# amp.net
KiCad netlist of a schematic drawn in Altium Designer
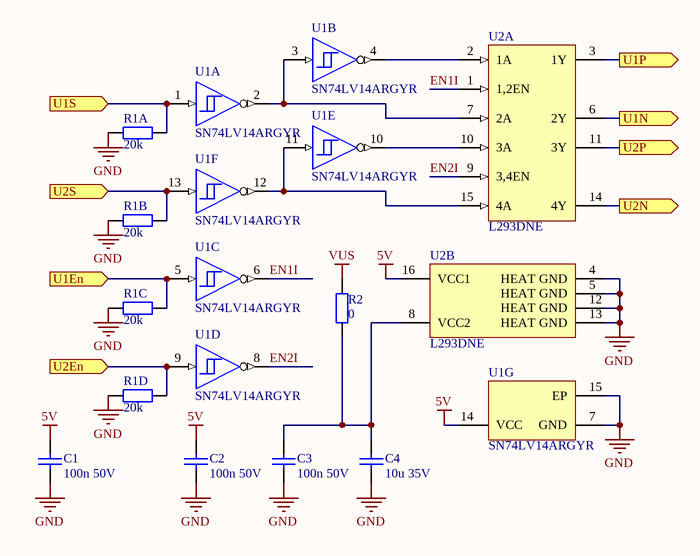
[diagram p0: amp.SchDoc]

(export (version "E")
  (design (tool "Eeschema 10.0.6"))
  (components
    (comp (ref "C1")
      (value "100n 50V")
      (footprint "C-0603-M")
      (description "Capacitor 100n 50V")
      (libsource (lib "Passives") (part "C-0603-100n-50V"))
    )
    (comp (ref "C2")
      (value "100n 50V")
      (footprint "C-0603-M")
      (description "Capacitor 100n 50V")
      (libsource (lib "Passives") (part "C-0603-100n-50V"))
    )
    (comp (ref "C3")
      (value "100n 50V")
      (footprint "C-0603-M")
      (description "Capacitor 100n 50V")
      (libsource (lib "Passives") (part "C-0603-100n-50V"))
    )
    (comp (ref "C4")
      (value "10u 35V")
      (footprint "C-0805-M")
      (description "3")
      (libsource (lib "Passives") (part "C-0805-10u-25V"))
    )
    (comp (ref "R1")
      (value "20k")
      (footprint "CAC-50P200X100-8N")
      (description "Resistor Array 4x20k")
      (libsource (lib "Passives") (part "R-4x20k"))
    )
    (comp (ref "R2")
      (value "0")
      (footprint "R-0603-M")
      (description "Resistor 0")
      (libsource (lib "Passives") (part "R-0603-0"))
    )
    (comp (ref "U1")
      (value "SN74LV14ARGYR")
      (footprint "RGY0014A_V")
      (description "Hex Schmitt-Trigger Inverters, RGY0014A, LARGE T&R")
      (fields
        (field (name "GENERIC PART NUMBER") "SN74LV14A")
        (field (name "MANUFACTURER") "Texas Instruments")
      )
      (libsource (lib "Altium Content Vault") (part "TI-SN74XXXXX4X-RGY0014A-14-SCHMITT"))
    )
    (comp (ref "U2")
      (value "L293DNE")
      (footprint "NE0016A")
      (fields (field (name "TOLERANCE") "10%"))
      (libsource (lib "Altium Content Vault") (part "TI-L293-NE16"))
    )
  )
  (nets
    (net (code "1") (name "/EN1I") (class "Default")
      (node (ref "U1") (pin "6") (pinfunction "~{3Y}_6") (pintype "output"))
      (node (ref "U2") (pin "1") (pinfunction "1,2EN_1") (pintype "input"))
    )
    (net (code "2") (name "/EN2I") (class "Default")
      (node (ref "U1") (pin "8") (pinfunction "~{4Y}_8") (pintype "output"))
      (node (ref "U2") (pin "9") (pinfunction "3,4EN_9") (pintype "input"))
    )
    (net (code "3") (name "/U1En") (class "Default")
      (node (ref "R1") (pin "6") (pinfunction "6_6") (pintype "passive"))
      (node (ref "U1") (pin "5") (pinfunction "3A_5") (pintype "input"))
    )
    (net (code "4") (name "/U1N") (class "Default")
      (node (ref "U2") (pin "6") (pinfunction "2Y_6") (pintype "tri_state"))
    )
    (net (code "5") (name "/U1P") (class "Default")
      (node (ref "U2") (pin "3") (pinfunction "1Y_3") (pintype "tri_state"))
    )
    (net (code "6") (name "/U1S") (class "Default")
      (node (ref "R1") (pin "8") (pinfunction "8_8") (pintype "passive"))
      (node (ref "U1") (pin "1") (pinfunction "1A_1") (pintype "input"))
    )
    (net (code "7") (name "/U2En") (class "Default")
      (node (ref "R1") (pin "5") (pinfunction "5_5") (pintype "passive"))
      (node (ref "U1") (pin "9") (pinfunction "4A_9") (pintype "input"))
    )
    (net (code "8") (name "/U2N") (class "Default")
      (node (ref "U2") (pin "14") (pinfunction "4Y_14") (pintype "tri_state"))
    )
    (net (code "9") (name "/U2P") (class "Default")
      (node (ref "U2") (pin "11") (pinfunction "3Y_11") (pintype "tri_state"))
    )
    (net (code "10") (name "/U2S") (class "Default")
      (node (ref "R1") (pin "7") (pinfunction "7_7") (pintype "passive"))
      (node (ref "U1") (pin "13") (pinfunction "6A_13") (pintype "input"))
    )
    (net (code "11") (name "5V") (class "Default")
      (node (ref "C1") (pin "2") (pinfunction "2_2") (pintype "passive"))
      (node (ref "C2") (pin "2") (pinfunction "2_2") (pintype "passive"))
      (node (ref "U1") (pin "14") (pinfunction "VCC_14") (pintype "power_in"))
      (node (ref "U2") (pin "16") (pinfunction "VCC1_16") (pintype "power_in"))
    )
    (net (code "12") (name "GND") (class "Default")
      (node (ref "C1") (pin "1") (pinfunction "1_1") (pintype "passive"))
      (node (ref "C2") (pin "1") (pinfunction "1_1") (pintype "passive"))
      (node (ref "C3") (pin "1") (pinfunction "1_1") (pintype "passive"))
      (node (ref "C4") (pin "1") (pinfunction "1_1") (pintype "passive"))
      (node (ref "R1") (pin "1") (pinfunction "1_1") (pintype "passive"))
      (node (ref "R1") (pin "2") (pinfunction "2_2") (pintype "passive"))
      (node (ref "R1") (pin "3") (pinfunction "3_3") (pintype "passive"))
      (node (ref "R1") (pin "4") (pinfunction "4_4") (pintype "passive"))
      (node (ref "U1") (pin "15") (pinfunction "EP_15") (pintype "passive"))
      (node (ref "U1") (pin "7") (pinfunction "GND_7") (pintype "power_in"))
      (node (ref "U2") (pin "12") (pinfunction "HEAT_GND_12") (pintype "power_in"))
      (node (ref "U2") (pin "13") (pinfunction "HEAT_GND_13") (pintype "power_in"))
      (node (ref "U2") (pin "4") (pinfunction "HEAT_GND_4") (pintype "power_in"))
      (node (ref "U2") (pin "5") (pinfunction "HEAT_GND_5") (pintype "power_in"))
    )
    (net (code "13") (name "Net-(U1A-~{1Y})") (class "Default")
      (node (ref "U1") (pin "2") (pinfunction "~{1Y}_2") (pintype "output"))
      (node (ref "U1") (pin "3") (pinfunction "2A_3") (pintype "input"))
      (node (ref "U2") (pin "7") (pinfunction "2A_7") (pintype "input"))
    )
    (net (code "14") (name "Net-(U1B-~{2Y})") (class "Default")
      (node (ref "U1") (pin "4") (pinfunction "~{2Y}_4") (pintype "output"))
      (node (ref "U2") (pin "2") (pinfunction "1A_2") (pintype "input"))
    )
    (net (code "15") (name "Net-(U1E-5A)") (class "Default")
      (node (ref "U1") (pin "11") (pinfunction "5A_11") (pintype "input"))
      (node (ref "U1") (pin "12") (pinfunction "~{6Y}_12") (pintype "output"))
      (node (ref "U2") (pin "15") (pinfunction "4A_15") (pintype "input"))
    )
    (net (code "16") (name "Net-(U1E-~{5Y})") (class "Default")
      (node (ref "U1") (pin "10") (pinfunction "~{5Y}_10") (pintype "output"))
      (node (ref "U2") (pin "10") (pinfunction "3A_10") (pintype "input"))
    )
    (net (code "17") (name "Net-(U2B-VCC2)") (class "Default")
      (node (ref "C3") (pin "2") (pinfunction "2_2") (pintype "passive"))
      (node (ref "C4") (pin "2") (pinfunction "2_2") (pintype "passive"))
      (node (ref "R2") (pin "1") (pinfunction "1_1") (pintype "passive"))
      (node (ref "U2") (pin "8") (pinfunction "VCC2_8") (pintype "power_in"))
    )
    (net (code "18") (name "VUS") (class "Default")
      (node (ref "R2") (pin "2") (pinfunction "2_2") (pintype "passive"))
    )
  )
)
